# SCH_mgts_sensor_node_2026-06-15.net
KiCad netlist of a schematic drawn in EasyEDA
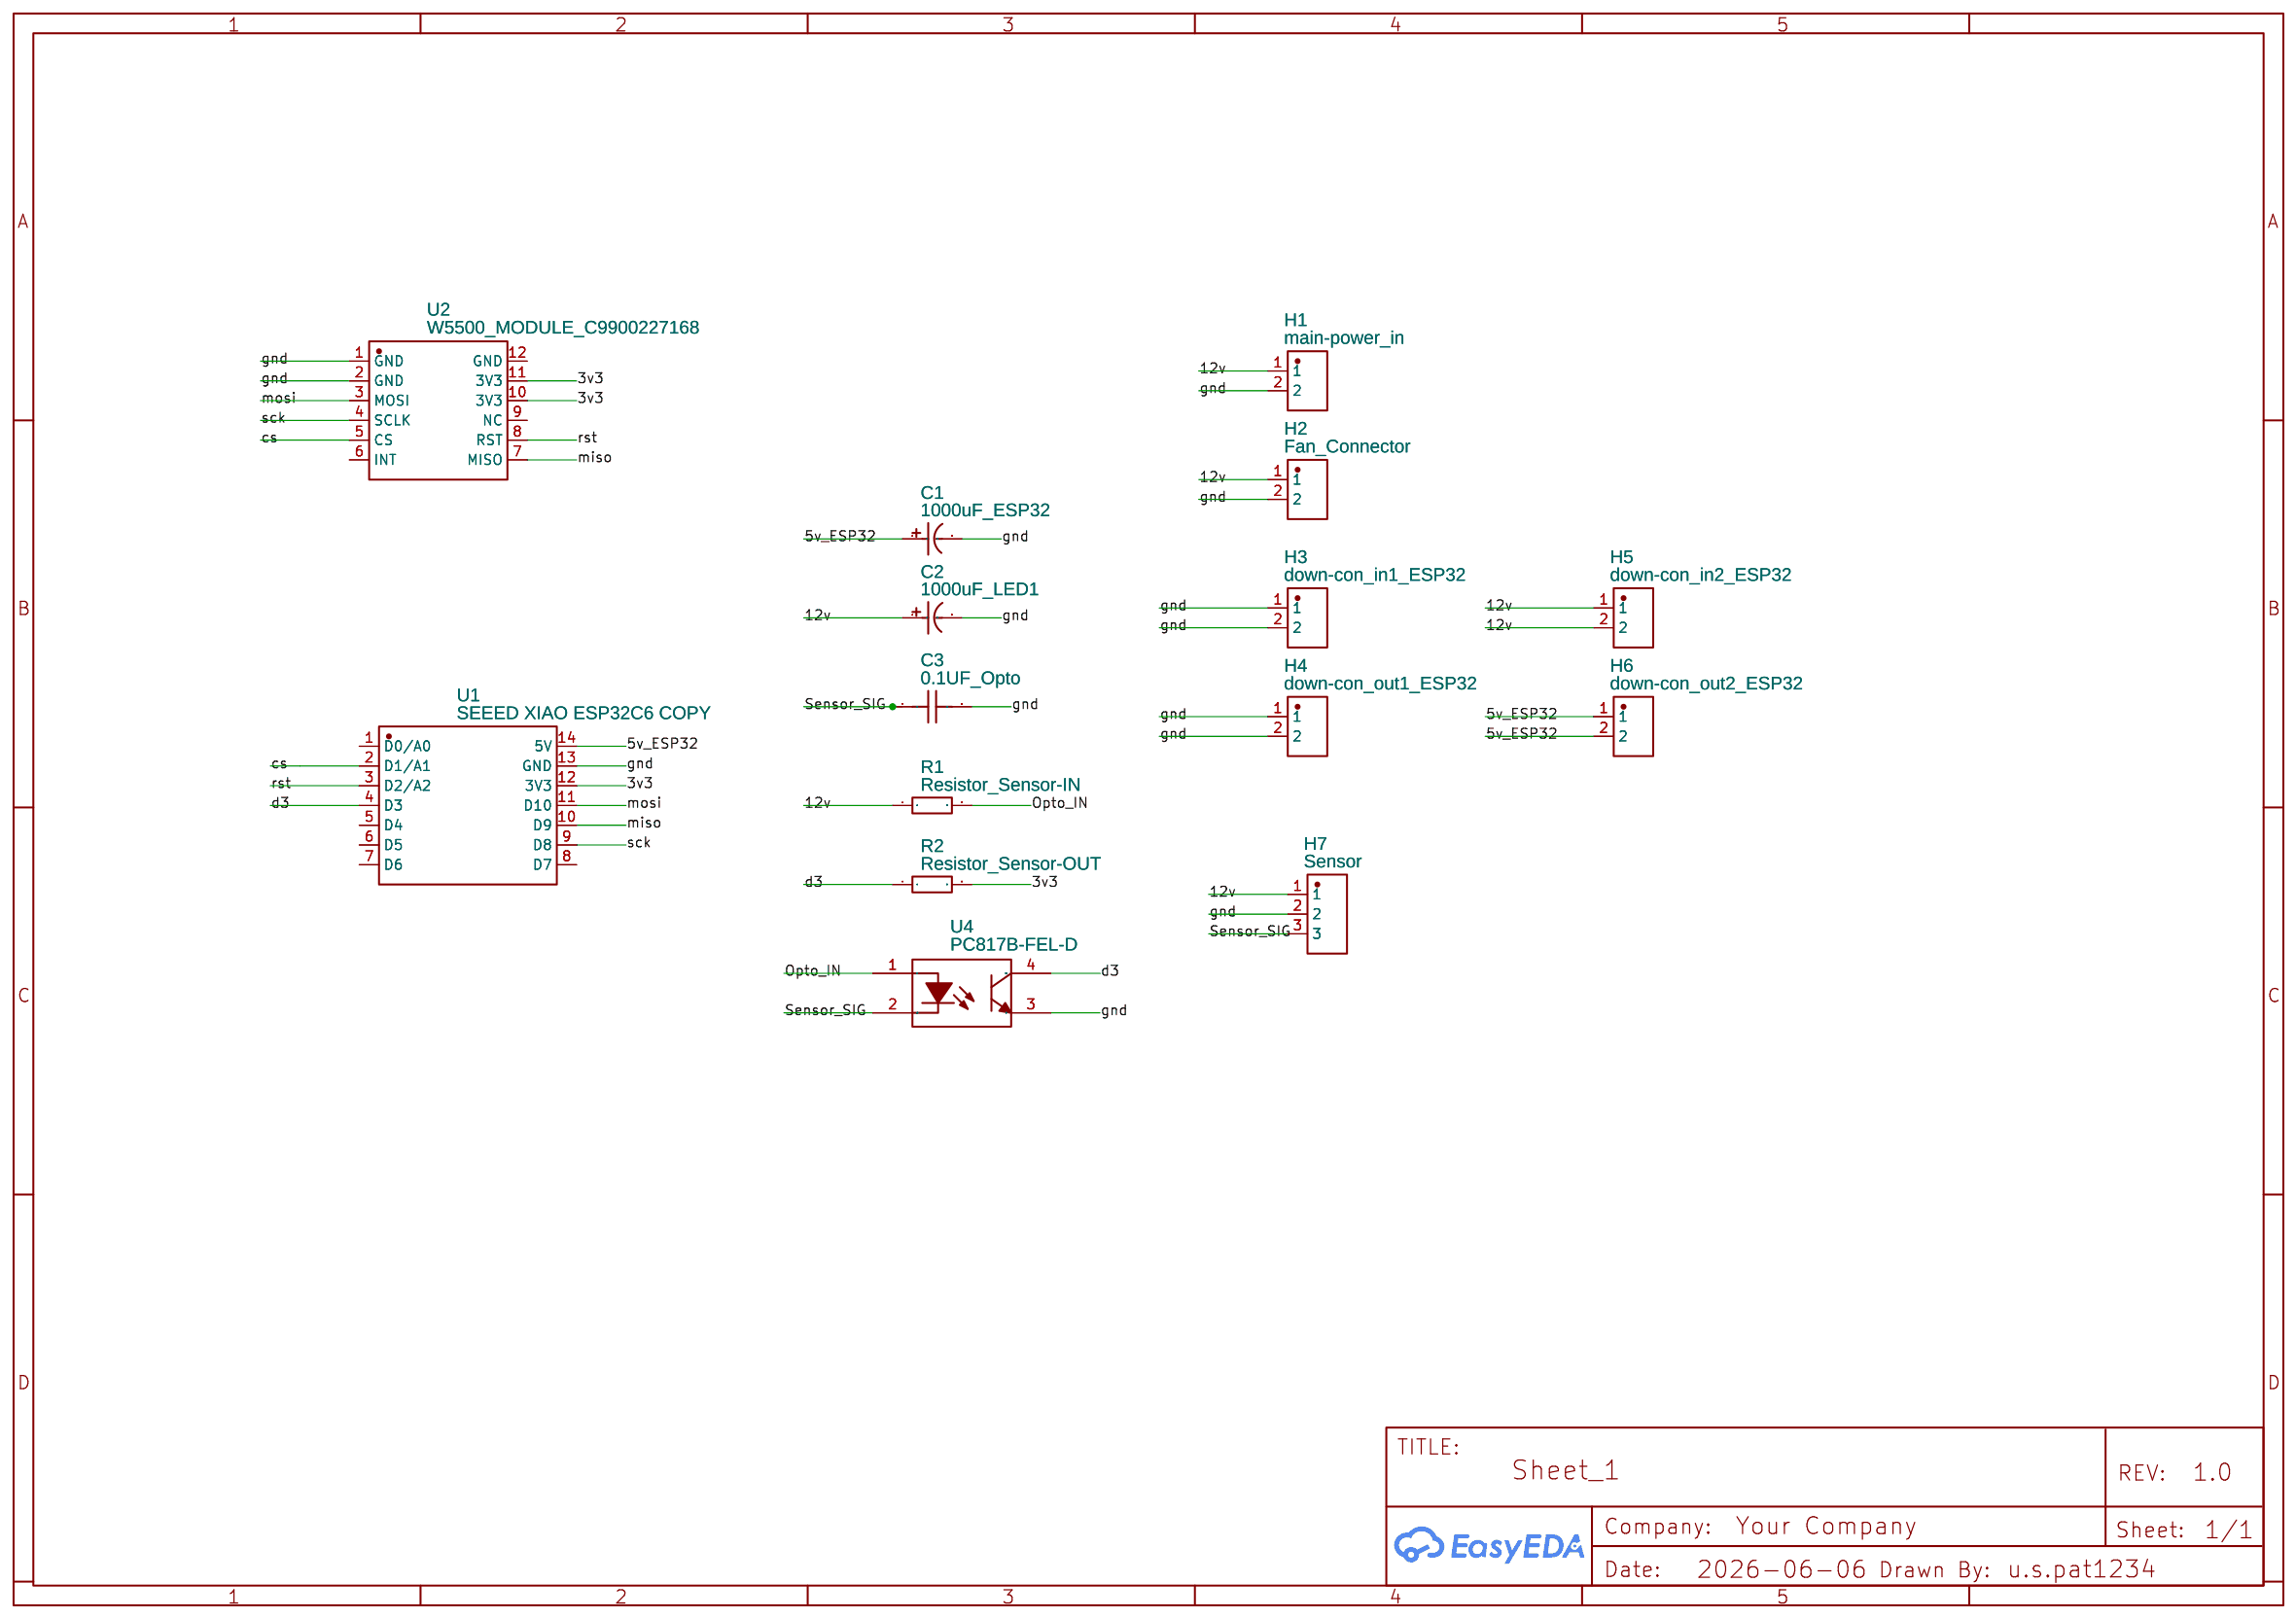
[diagram p0: schematic sheet]

(export (version "E")
  (design (tool "Eeschema 10.0.6"))
  (components
    (comp (ref "C1")
      (value "1000uF_ESP32")
      (fields (field (name "Manufacturer Part") "1000uF"))
      (libsource (lib "") (part "1000uF"))
    )
    (comp (ref "C2")
      (value "1000uF_LED1")
      (fields (field (name "Manufacturer Part") "1000uF"))
      (libsource (lib "") (part "1000uF"))
    )
    (comp (ref "C3")
      (value "0.1UF_Opto")
      (fields
        (field (name "Manufacturer Part") "250V 0.1UF 5% CBBCapacitor")
        (field (name "Manufacturer") "ReliaPro")
      )
      (libsource (lib "") (part "250V 0.1UF 5% CBBCapacitor"))
    )
    (comp (ref "H1")
      (value "main-power_in")
      (fields
        (field (name "Manufacturer Part") "KH-2.54PH90-1X2P-L13.8")
        (field (name "Manufacturer") "kinghelm(金航标)")
      )
      (libsource (lib "") (part "KH-2.54PH90-1X2P-L13.8"))
    )
    (comp (ref "H2")
      (value "Fan_Connector")
      (fields
        (field (name "Manufacturer Part") "KH-2.54PH90-1X2P-L13.8")
        (field (name "Manufacturer") "kinghelm(金航标)")
      )
      (libsource (lib "") (part "KH-2.54PH90-1X2P-L13.8"))
    )
    (comp (ref "H3")
      (value "down-con_in1_ESP32")
      (fields
        (field (name "Manufacturer Part") "KH-2.54PH90-1X2P-L13.8")
        (field (name "Manufacturer") "kinghelm(金航标)")
      )
      (libsource (lib "") (part "KH-2.54PH90-1X2P-L13.8"))
    )
    (comp (ref "H4")
      (value "down-con_out1_ESP32")
      (fields
        (field (name "Manufacturer Part") "KH-2.54PH90-1X2P-L13.8")
        (field (name "Manufacturer") "kinghelm(金航标)")
      )
      (libsource (lib "") (part "KH-2.54PH90-1X2P-L13.8"))
    )
    (comp (ref "H5")
      (value "down-con_in2_ESP32")
      (fields
        (field (name "Manufacturer Part") "KH-2.54PH90-1X2P-L13.8")
        (field (name "Manufacturer") "kinghelm(金航标)")
      )
      (libsource (lib "") (part "KH-2.54PH90-1X2P-L13.8"))
    )
    (comp (ref "H6")
      (value "down-con_out2_ESP32")
      (fields
        (field (name "Manufacturer Part") "KH-2.54PH90-1X2P-L13.8")
        (field (name "Manufacturer") "kinghelm(金航标)")
      )
      (libsource (lib "") (part "KH-2.54PH90-1X2P-L13.8"))
    )
    (comp (ref "H7")
      (value "Sensor")
      (fields (field (name "Manufacturer Part") "XY-2.54-1*3PZ") (field (name "Manufacturer") "XYECONN(辛译)"))
      (libsource (lib "") (part "XY-2.54-1*3PZ"))
    )
    (comp (ref "R1")
      (value "Resistor_Sensor-IN")
      (fields (field (name "Manufacturer Part") "1K-AXIAL-0.4"))
      (libsource (lib "") (part "1K-AXIAL-0.4"))
    )
    (comp (ref "R2")
      (value "Resistor_Sensor-OUT")
      (fields (field (name "Manufacturer Part") "1K-AXIAL-0.4"))
      (libsource (lib "") (part "1K-AXIAL-0.4"))
    )
    (comp (ref "U1")
      (value "SEEED XIAO ESP32C6 COPY")
      (fields (field (name "Manufacturer Part") "XIAO ESP32C6") (field (name "Manufacturer") "Seeed Studio"))
      (libsource (lib "") (part "SEEED XIAO ESP32C6 COPY"))
    )
    (comp (ref "U2")
      (value "W5500_MODULE_C9900227168")
      (fields (field (name "Manufacturer Part") "W5500_MODULE"))
      (libsource (lib "") (part "W5500_MODULE_C9900227168"))
    )
    (comp (ref "U4")
      (value "PC817B-FEL-D")
      (fields (field (name "Manufacturer") "DDF(鼎德丰)"))
      (libsource (lib "") (part "PC817B-FEL-D"))
    )
  )
  (nets
    (net (code "1") (name "/3v3") (class "Default")
      (node (ref "R2") (pin "2") (pinfunction "2_2") (pintype "unspecified"))
      (node (ref "U1") (pin "12") (pinfunction "3V3_12") (pintype "unspecified"))
      (node (ref "U2") (pin "10") (pinfunction "3V3_10") (pintype "unspecified"))
      (node (ref "U2") (pin "11") (pinfunction "3V3_11") (pintype "unspecified"))
    )
    (net (code "2") (name "/5v_ESP32") (class "Default")
      (node (ref "C1") (pin "1") (pinfunction "1_1") (pintype "input"))
      (node (ref "H6") (pin "1") (pinfunction "1_1") (pintype "unspecified"))
      (node (ref "H6") (pin "2") (pinfunction "2_2") (pintype "unspecified"))
      (node (ref "U1") (pin "14") (pinfunction "5V_14") (pintype "unspecified"))
    )
    (net (code "3") (name "/12v") (class "Default")
      (node (ref "C2") (pin "1") (pinfunction "1_1") (pintype "input"))
      (node (ref "H1") (pin "1") (pinfunction "1_1") (pintype "unspecified"))
      (node (ref "H2") (pin "1") (pinfunction "1_1") (pintype "unspecified"))
      (node (ref "H5") (pin "1") (pinfunction "1_1") (pintype "unspecified"))
      (node (ref "H5") (pin "2") (pinfunction "2_2") (pintype "unspecified"))
      (node (ref "H7") (pin "1") (pinfunction "1_1") (pintype "unspecified"))
      (node (ref "R1") (pin "1") (pinfunction "1_1") (pintype "unspecified"))
    )
    (net (code "4") (name "/Opto_IN") (class "Default")
      (node (ref "R1") (pin "2") (pinfunction "2_2") (pintype "unspecified"))
      (node (ref "U4") (pin "1") (pinfunction "AN_1") (pintype "unspecified"))
    )
    (net (code "5") (name "/Sensor_SIG") (class "Default")
      (node (ref "C3") (pin "1") (pinfunction "1_1") (pintype "unspecified"))
      (node (ref "H7") (pin "3") (pinfunction "3_3") (pintype "unspecified"))
      (node (ref "U4") (pin "2") (pinfunction "CAT_2") (pintype "unspecified"))
    )
    (net (code "6") (name "/cs") (class "Default")
      (node (ref "U1") (pin "2") (pinfunction "D1/A1_2") (pintype "unspecified"))
      (node (ref "U2") (pin "5") (pinfunction "CS_5") (pintype "unspecified"))
    )
    (net (code "7") (name "/d3") (class "Default")
      (node (ref "R2") (pin "1") (pinfunction "1_1") (pintype "unspecified"))
      (node (ref "U1") (pin "4") (pinfunction "D3_4") (pintype "unspecified"))
      (node (ref "U4") (pin "4") (pinfunction "COL_4") (pintype "unspecified"))
    )
    (net (code "8") (name "/gnd") (class "Default")
      (node (ref "C1") (pin "2") (pinfunction "2_2") (pintype "input"))
      (node (ref "C2") (pin "2") (pinfunction "2_2") (pintype "input"))
      (node (ref "C3") (pin "2") (pinfunction "2_2") (pintype "unspecified"))
      (node (ref "H1") (pin "2") (pinfunction "2_2") (pintype "unspecified"))
      (node (ref "H2") (pin "2") (pinfunction "2_2") (pintype "unspecified"))
      (node (ref "H3") (pin "1") (pinfunction "1_1") (pintype "unspecified"))
      (node (ref "H3") (pin "2") (pinfunction "2_2") (pintype "unspecified"))
      (node (ref "H4") (pin "1") (pinfunction "1_1") (pintype "unspecified"))
      (node (ref "H4") (pin "2") (pinfunction "2_2") (pintype "unspecified"))
      (node (ref "H7") (pin "2") (pinfunction "2_2") (pintype "unspecified"))
      (node (ref "U1") (pin "13") (pinfunction "GND_13") (pintype "unspecified"))
      (node (ref "U2") (pin "1") (pinfunction "GND_1") (pintype "unspecified"))
      (node (ref "U2") (pin "2") (pinfunction "GND_2") (pintype "unspecified"))
      (node (ref "U4") (pin "3") (pinfunction "EM_3") (pintype "unspecified"))
    )
    (net (code "9") (name "/miso") (class "Default")
      (node (ref "U1") (pin "10") (pinfunction "D9_10") (pintype "unspecified"))
      (node (ref "U2") (pin "7") (pinfunction "MISO_7") (pintype "unspecified"))
    )
    (net (code "10") (name "/mosi") (class "Default")
      (node (ref "U1") (pin "11") (pinfunction "D10_11") (pintype "unspecified"))
      (node (ref "U2") (pin "3") (pinfunction "MOSI_3") (pintype "unspecified"))
    )
    (net (code "11") (name "/rst") (class "Default")
      (node (ref "U1") (pin "3") (pinfunction "D2/A2_3") (pintype "unspecified"))
      (node (ref "U2") (pin "8") (pinfunction "RST_8") (pintype "unspecified"))
    )
    (net (code "12") (name "/sck") (class "Default")
      (node (ref "U1") (pin "9") (pinfunction "D8_9") (pintype "unspecified"))
      (node (ref "U2") (pin "4") (pinfunction "SCLK_4") (pintype "unspecified"))
    )
    (net (code "13") (name "unconnected-(U1-D0{slash}A0-Pad1)") (class "Default")
      (node (ref "U1") (pin "1") (pinfunction "D0/A0_1") (pintype "unspecified"))
    )
    (net (code "14") (name "unconnected-(U1-D4-Pad5)") (class "Default")
      (node (ref "U1") (pin "5") (pinfunction "D4_5") (pintype "unspecified"))
    )
    (net (code "15") (name "unconnected-(U1-D5-Pad6)") (class "Default")
      (node (ref "U1") (pin "6") (pinfunction "D5_6") (pintype "unspecified"))
    )
    (net (code "16") (name "unconnected-(U1-D6-Pad7)") (class "Default")
      (node (ref "U1") (pin "7") (pinfunction "D6_7") (pintype "unspecified"))
    )
    (net (code "17") (name "unconnected-(U1-D7-Pad8)") (class "Default")
      (node (ref "U1") (pin "8") (pinfunction "D7_8") (pintype "unspecified"))
    )
    (net (code "18") (name "unconnected-(U2-GND-Pad12)") (class "Default")
      (node (ref "U2") (pin "12") (pinfunction "GND_12") (pintype "unspecified"))
    )
    (net (code "19") (name "unconnected-(U2-INT-Pad6)") (class "Default")
      (node (ref "U2") (pin "6") (pinfunction "INT_6") (pintype "unspecified"))
    )
    (net (code "20") (name "unconnected-(U2-NC-Pad9)") (class "Default")
      (node (ref "U2") (pin "9") (pinfunction "NC_9") (pintype "unspecified"))
    )
  )
)
